# ISP_CONNECTORS.net
KiCad netlist of a schematic drawn in Altium Designer
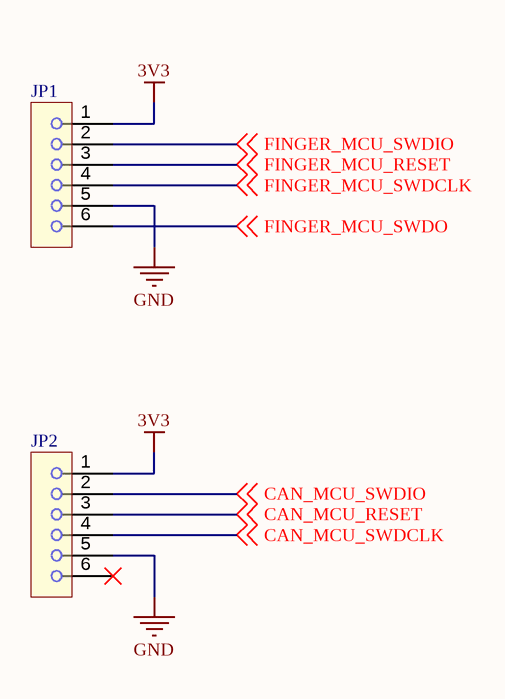
[diagram p0: ISP_CONNECTORS.SchDoc]

(export (version "E")
  (design (tool "Eeschema 10.0.6"))
  (components
    (comp (ref "JP1")
      (value "TC2030-6-NL-FOOTPRINT")
      (footprint "TAG_TC2030_NL_6")
      (description "CONN, FP, 2X3, .05, DEBUG, SMT")
      (fields (field (name "MANUFACTURER") "NO PART") (field (name "PART NUMBER") "FOOTPRINT ONLY"))
      (libsource (lib "Phalanx") (part "TC2030-6-NL-FOOTPRINT"))
    )
    (comp (ref "JP2")
      (value "TC2030-6-NL-FOOTPRINT")
      (footprint "TAG_TC2030_NL_6")
      (description "CONN, FP, 2X3, .05, DEBUG, SMT")
      (fields (field (name "MANUFACTURER") "NO PART") (field (name "PART NUMBER") "FOOTPRINT ONLY"))
      (libsource (lib "Phalanx") (part "TC2030-6-NL-FOOTPRINT"))
    )
  )
  (nets
    (net (code "1") (name "3V3") (class "Default")
      (node (ref "JP1") (pin "1") (pinfunction "1_1") (pintype "passive"))
      (node (ref "JP2") (pin "1") (pinfunction "1_1") (pintype "passive"))
    )
    (net (code "2") (name "CAN_MCU_RESET") (class "Default")
      (node (ref "JP2") (pin "3") (pinfunction "3_3") (pintype "passive"))
    )
    (net (code "3") (name "CAN_MCU_SWDCLK") (class "Default")
      (node (ref "JP2") (pin "4") (pinfunction "4_4") (pintype "passive"))
    )
    (net (code "4") (name "CAN_MCU_SWDIO") (class "Default")
      (node (ref "JP2") (pin "2") (pinfunction "2_2") (pintype "passive"))
    )
    (net (code "5") (name "FINGER_MCU_RESET") (class "Default")
      (node (ref "JP1") (pin "3") (pinfunction "3_3") (pintype "passive"))
    )
    (net (code "6") (name "FINGER_MCU_SWDCLK") (class "Default")
      (node (ref "JP1") (pin "4") (pinfunction "4_4") (pintype "passive"))
    )
    (net (code "7") (name "FINGER_MCU_SWDIO") (class "Default")
      (node (ref "JP1") (pin "2") (pinfunction "2_2") (pintype "passive"))
    )
    (net (code "8") (name "FINGER_MCU_SWDO") (class "Default")
      (node (ref "JP1") (pin "6") (pinfunction "6_6") (pintype "passive"))
    )
    (net (code "9") (name "GND") (class "Default")
      (node (ref "JP1") (pin "5") (pinfunction "5_5") (pintype "passive"))
      (node (ref "JP2") (pin "5") (pinfunction "5_5") (pintype "passive"))
    )
    (net (code "10") (name "unconnected-(JP2-Pad6)") (class "Default")
      (node (ref "JP2") (pin "6") (pinfunction "6_6") (pintype "passive+no_connect"))
    )
  )
)
